# 2_Isolation.net
KiCad netlist of a schematic drawn in Altium Designer
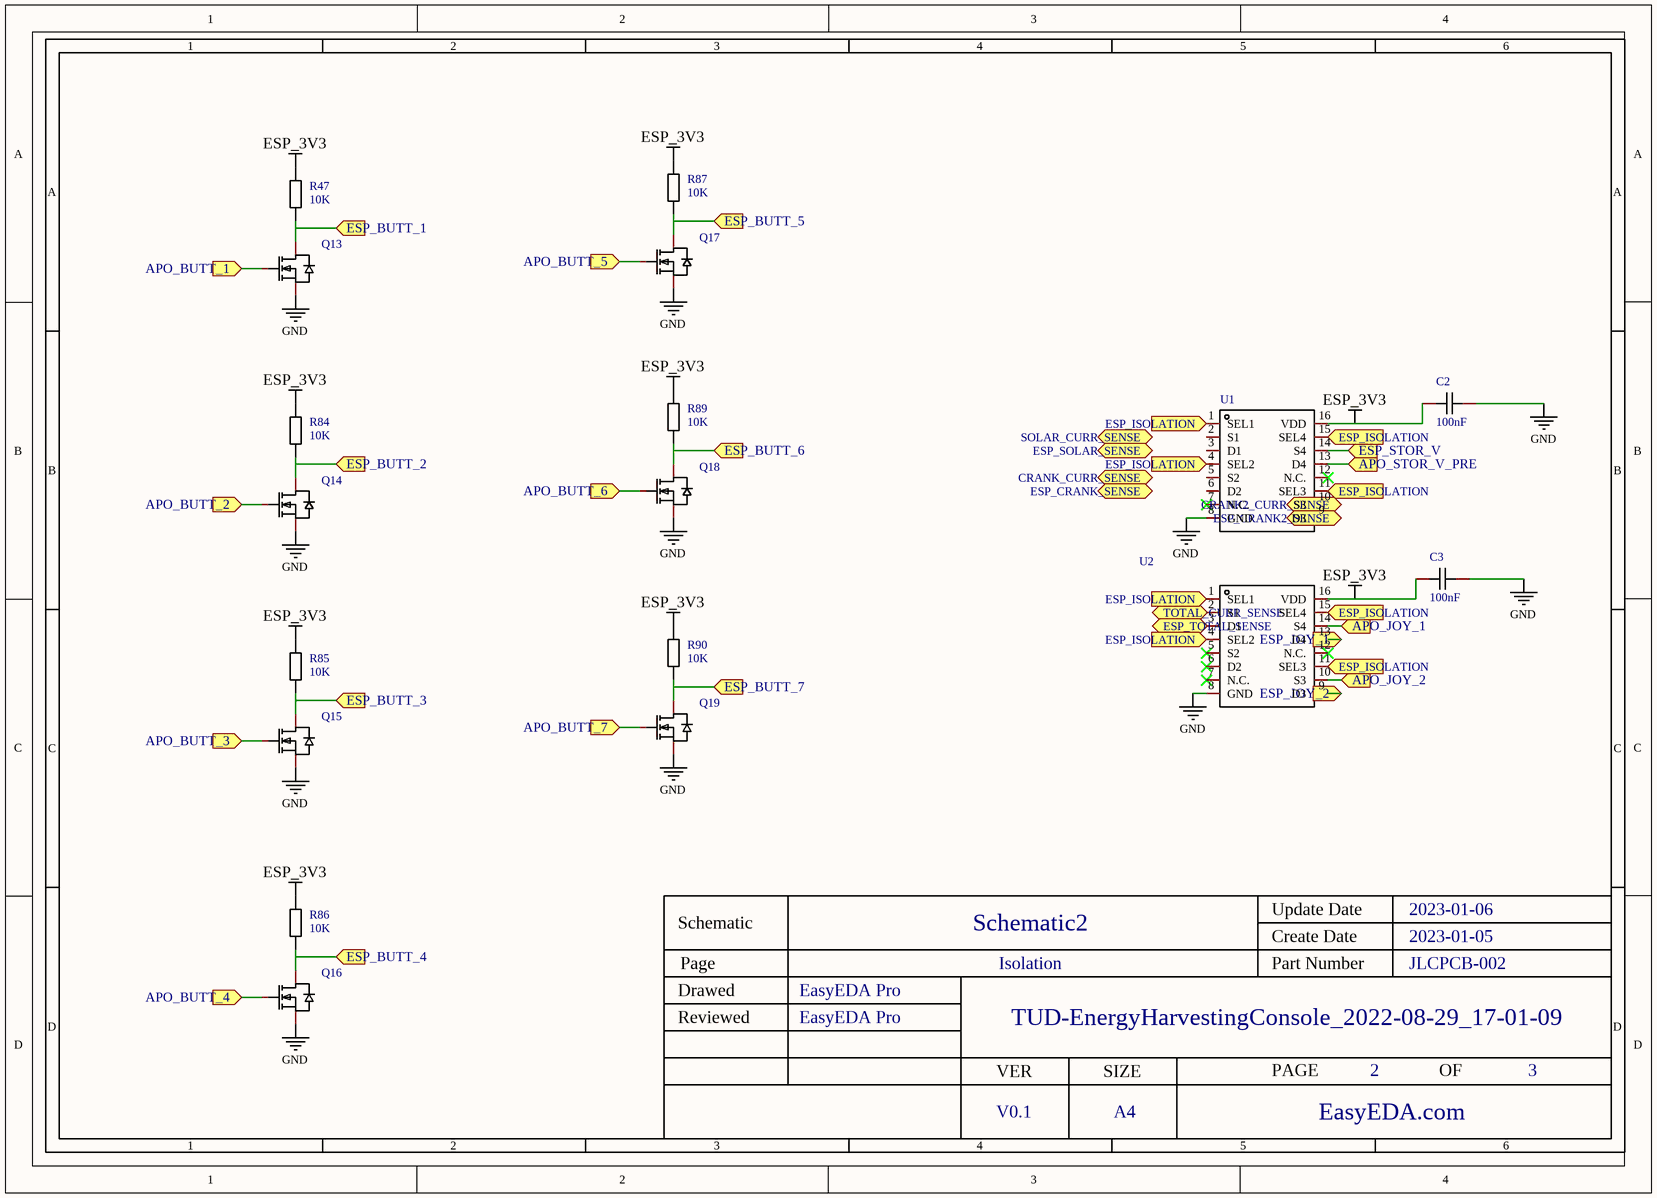
[diagram p0: 2_Isolation.schdoc]

(export (version "E")
  (design (tool "Eeschema 10.0.6"))
  (components
    (comp (ref "C2")
      (value "100nF")
      (fields
        (field (name "NAME") "100nF")
        (field (name "MANUFACTURER") "YAGEO")
        (field (name "MANUFACTURER PART") "CC0603KRX7R9BB104")
      )
      (libsource (lib "altium-import") (part "root_2_CC0603KRX7R9BB104_"))
    )
    (comp (ref "C3")
      (value "100nF")
      (fields
        (field (name "NAME") "100nF")
        (field (name "MANUFACTURER") "YAGEO")
        (field (name "MANUFACTURER PART") "CC0603KRX7R9BB104")
      )
      (libsource (lib "altium-import") (part "root_0_CC0603KRX7R9BB104_"))
    )
    (comp (ref "Q13")
      (value "SI2302")
      (fields (field (name "MANUFACTURER") "YONGYUTAI(永裕泰)"))
      (libsource (lib "altium-import") (part "root_0_SI2302_"))
    )
    (comp (ref "Q14")
      (value "SI2302")
      (fields (field (name "MANUFACTURER") "YONGYUTAI(永裕泰)"))
      (libsource (lib "altium-import") (part "root_0_SI2302_"))
    )
    (comp (ref "Q15")
      (value "SI2302")
      (fields (field (name "MANUFACTURER") "YONGYUTAI(永裕泰)"))
      (libsource (lib "altium-import") (part "root_0_SI2302_"))
    )
    (comp (ref "Q16")
      (value "SI2302")
      (fields (field (name "MANUFACTURER") "YONGYUTAI(永裕泰)"))
      (libsource (lib "altium-import") (part "root_0_SI2302_"))
    )
    (comp (ref "Q17")
      (value "SI2302")
      (fields (field (name "MANUFACTURER") "YONGYUTAI(永裕泰)"))
      (libsource (lib "altium-import") (part "root_0_SI2302_"))
    )
    (comp (ref "Q18")
      (value "SI2302")
      (fields (field (name "MANUFACTURER") "YONGYUTAI(永裕泰)"))
      (libsource (lib "altium-import") (part "root_0_SI2302_"))
    )
    (comp (ref "Q19")
      (value "SI2302")
      (fields (field (name "MANUFACTURER") "YONGYUTAI(永裕泰)"))
      (libsource (lib "altium-import") (part "root_0_SI2302_"))
    )
    (comp (ref "R47")
      (value "10K")
      (fields
        (field (name "NAME") "10K")
        (field (name "MANUFACTURER") "UniOhm")
        (field (name "MANUFACTURER PART") "0603WAF1002T5E")
      )
      (libsource (lib "altium-import") (part "root_3_0603WAF1002T5E_"))
    )
    (comp (ref "R84")
      (value "10K")
      (fields
        (field (name "NAME") "10K")
        (field (name "MANUFACTURER") "UniOhm")
        (field (name "MANUFACTURER PART") "0603WAF1002T5E")
      )
      (libsource (lib "altium-import") (part "root_3_0603WAF1002T5E_"))
    )
    (comp (ref "R85")
      (value "10K")
      (fields
        (field (name "NAME") "10K")
        (field (name "MANUFACTURER") "UniOhm")
        (field (name "MANUFACTURER PART") "0603WAF1002T5E")
      )
      (libsource (lib "altium-import") (part "root_3_0603WAF1002T5E_"))
    )
    (comp (ref "R86")
      (value "10K")
      (fields
        (field (name "NAME") "10K")
        (field (name "MANUFACTURER") "UniOhm")
        (field (name "MANUFACTURER PART") "0603WAF1002T5E")
      )
      (libsource (lib "altium-import") (part "root_3_0603WAF1002T5E_"))
    )
    (comp (ref "R87")
      (value "10K")
      (fields
        (field (name "NAME") "10K")
        (field (name "MANUFACTURER") "UniOhm")
        (field (name "MANUFACTURER PART") "0603WAF1002T5E")
      )
      (libsource (lib "altium-import") (part "root_3_0603WAF1002T5E_"))
    )
    (comp (ref "R89")
      (value "10K")
      (fields
        (field (name "NAME") "10K")
        (field (name "MANUFACTURER") "UniOhm")
        (field (name "MANUFACTURER PART") "0603WAF1002T5E")
      )
      (libsource (lib "altium-import") (part "root_3_0603WAF1002T5E_"))
    )
    (comp (ref "R90")
      (value "10K")
      (fields
        (field (name "NAME") "10K")
        (field (name "MANUFACTURER") "UniOhm")
        (field (name "MANUFACTURER PART") "0603WAF1002T5E")
      )
      (libsource (lib "altium-import") (part "root_3_0603WAF1002T5E_"))
    )
    (comp (ref "U1")
      (value "TMUX1511RSVR")
      (description "Switch Circuit:-")
      (fields (field (name "MANUFACTURER") "TI(德州仪器)"))
      (libsource (lib "altium-import") (part "root_0_TMUX1511RSVR_"))
    )
    (comp (ref "U2")
      (value "TMUX1511RSVR")
      (description "Switch Circuit:-")
      (fields (field (name "MANUFACTURER") "TI(德州仪器)"))
      (libsource (lib "altium-import") (part "root_0_TMUX1511RSVR_"))
    )
  )
  (nets
    (net (code "1") (name "/APO_BUTT_1") (class "Default")
      (node (ref "Q13") (pin "1") (pinfunction "G_1") (pintype "passive"))
    )
    (net (code "2") (name "/APO_BUTT_2") (class "Default")
      (node (ref "Q14") (pin "1") (pinfunction "G_1") (pintype "passive"))
    )
    (net (code "3") (name "/APO_BUTT_3") (class "Default")
      (node (ref "Q15") (pin "1") (pinfunction "G_1") (pintype "passive"))
    )
    (net (code "4") (name "/APO_BUTT_4") (class "Default")
      (node (ref "Q16") (pin "1") (pinfunction "G_1") (pintype "passive"))
    )
    (net (code "5") (name "/APO_BUTT_5") (class "Default")
      (node (ref "Q17") (pin "1") (pinfunction "G_1") (pintype "passive"))
    )
    (net (code "6") (name "/APO_BUTT_6") (class "Default")
      (node (ref "Q18") (pin "1") (pinfunction "G_1") (pintype "passive"))
    )
    (net (code "7") (name "/APO_BUTT_7") (class "Default")
      (node (ref "Q19") (pin "1") (pinfunction "G_1") (pintype "passive"))
    )
    (net (code "8") (name "/APO_JOY_1") (class "Default")
      (node (ref "U2") (pin "14") (pinfunction "S4_14") (pintype "passive"))
    )
    (net (code "9") (name "/APO_JOY_2") (class "Default")
      (node (ref "U2") (pin "10") (pinfunction "S3_10") (pintype "passive"))
    )
    (net (code "10") (name "/APO_STOR_V_PRE") (class "Default")
      (node (ref "U1") (pin "13") (pinfunction "D4_13") (pintype "passive"))
    )
    (net (code "13") (name "/ESP_BUTT_1") (class "Default")
      (node (ref "Q13") (pin "3") (pinfunction "D_3") (pintype "passive"))
      (node (ref "R47") (pin "2") (pinfunction "2_2") (pintype "passive"))
    )
    (net (code "14") (name "/ESP_BUTT_2") (class "Default")
      (node (ref "Q14") (pin "3") (pinfunction "D_3") (pintype "passive"))
      (node (ref "R84") (pin "2") (pinfunction "2_2") (pintype "passive"))
    )
    (net (code "15") (name "/ESP_BUTT_3") (class "Default")
      (node (ref "Q15") (pin "3") (pinfunction "D_3") (pintype "passive"))
      (node (ref "R85") (pin "2") (pinfunction "2_2") (pintype "passive"))
    )
    (net (code "16") (name "/ESP_BUTT_4") (class "Default")
      (node (ref "Q16") (pin "3") (pinfunction "D_3") (pintype "passive"))
      (node (ref "R86") (pin "2") (pinfunction "2_2") (pintype "passive"))
    )
    (net (code "17") (name "/ESP_BUTT_5") (class "Default")
      (node (ref "Q17") (pin "3") (pinfunction "D_3") (pintype "passive"))
      (node (ref "R87") (pin "2") (pinfunction "2_2") (pintype "passive"))
    )
    (net (code "18") (name "/ESP_BUTT_6") (class "Default")
      (node (ref "Q18") (pin "3") (pinfunction "D_3") (pintype "passive"))
      (node (ref "R89") (pin "2") (pinfunction "2_2") (pintype "passive"))
    )
    (net (code "19") (name "/ESP_BUTT_7") (class "Default")
      (node (ref "Q19") (pin "3") (pinfunction "D_3") (pintype "passive"))
      (node (ref "R90") (pin "2") (pinfunction "2_2") (pintype "passive"))
    )
    (net (code "22") (name "/ESP_ISOLATION") (class "Default")
      (node (ref "U1") (pin "1") (pinfunction "SEL1_1") (pintype "passive"))
      (node (ref "U1") (pin "11") (pinfunction "SEL3_11") (pintype "passive"))
      (node (ref "U1") (pin "15") (pinfunction "SEL4_15") (pintype "passive"))
      (node (ref "U1") (pin "4") (pinfunction "SEL2_4") (pintype "passive"))
      (node (ref "U2") (pin "1") (pinfunction "SEL1_1") (pintype "passive"))
      (node (ref "U2") (pin "11") (pinfunction "SEL3_11") (pintype "passive"))
      (node (ref "U2") (pin "15") (pinfunction "SEL4_15") (pintype "passive"))
      (node (ref "U2") (pin "4") (pinfunction "SEL2_4") (pintype "passive"))
    )
    (net (code "23") (name "/ESP_JOY_1") (class "Default")
      (node (ref "U2") (pin "13") (pinfunction "D4_13") (pintype "passive"))
    )
    (net (code "24") (name "/ESP_JOY_2") (class "Default")
      (node (ref "U2") (pin "9") (pinfunction "D3_9") (pintype "passive"))
    )
    (net (code "26") (name "/ESP_STOR_V") (class "Default")
      (node (ref "U1") (pin "14") (pinfunction "S4_14") (pintype "passive"))
    )
    (net (code "30") (name "ESP_3V3") (class "Default")
      (node (ref "C2") (pin "2") (pinfunction "2_2") (pintype "passive"))
      (node (ref "C3") (pin "1") (pinfunction "1_1") (pintype "passive"))
      (node (ref "R47") (pin "1") (pinfunction "1_1") (pintype "passive"))
      (node (ref "R84") (pin "1") (pinfunction "1_1") (pintype "passive"))
      (node (ref "R85") (pin "1") (pinfunction "1_1") (pintype "passive"))
      (node (ref "R86") (pin "1") (pinfunction "1_1") (pintype "passive"))
      (node (ref "R87") (pin "1") (pinfunction "1_1") (pintype "passive"))
      (node (ref "R89") (pin "1") (pinfunction "1_1") (pintype "passive"))
      (node (ref "R90") (pin "1") (pinfunction "1_1") (pintype "passive"))
      (node (ref "U1") (pin "16") (pinfunction "VDD_16") (pintype "passive"))
      (node (ref "U2") (pin "16") (pinfunction "VDD_16") (pintype "passive"))
    )
    (net (code "31") (name "GND") (class "Default")
      (node (ref "C2") (pin "1") (pinfunction "1_1") (pintype "passive"))
      (node (ref "C3") (pin "2") (pinfunction "2_2") (pintype "passive"))
      (node (ref "Q13") (pin "2") (pinfunction "S_2") (pintype "passive"))
      (node (ref "Q14") (pin "2") (pinfunction "S_2") (pintype "passive"))
      (node (ref "Q15") (pin "2") (pinfunction "S_2") (pintype "passive"))
      (node (ref "Q16") (pin "2") (pinfunction "S_2") (pintype "passive"))
      (node (ref "Q17") (pin "2") (pinfunction "S_2") (pintype "passive"))
      (node (ref "Q18") (pin "2") (pinfunction "S_2") (pintype "passive"))
      (node (ref "Q19") (pin "2") (pinfunction "S_2") (pintype "passive"))
      (node (ref "U1") (pin "8") (pinfunction "GND_8") (pintype "passive"))
      (node (ref "U2") (pin "8") (pinfunction "GND_8") (pintype "passive"))
    )
    (net (code "32") (name "unconnected-(U1-D1-Pad3)") (class "Default")
      (node (ref "U1") (pin "3") (pinfunction "D1_3") (pintype "passive"))
    )
    (net (code "33") (name "unconnected-(U1-D2-Pad6)") (class "Default")
      (node (ref "U1") (pin "6") (pinfunction "D2_6") (pintype "passive"))
    )
    (net (code "34") (name "unconnected-(U1-D3-Pad9)") (class "Default")
      (node (ref "U1") (pin "9") (pinfunction "D3_9") (pintype "passive"))
    )
    (net (code "35") (name "unconnected-(U1-N.C.-Pad7)") (class "Default")
      (node (ref "U1") (pin "7") (pinfunction "N.C._7") (pintype "passive+no_connect"))
    )
    (net (code "36") (name "unconnected-(U1-N.C.-Pad12)") (class "Default")
      (node (ref "U1") (pin "12") (pinfunction "N.C._12") (pintype "passive+no_connect"))
    )
    (net (code "37") (name "unconnected-(U1-S1-Pad2)") (class "Default")
      (node (ref "U1") (pin "2") (pinfunction "S1_2") (pintype "passive"))
    )
    (net (code "38") (name "unconnected-(U1-S2-Pad5)") (class "Default")
      (node (ref "U1") (pin "5") (pinfunction "S2_5") (pintype "passive"))
    )
    (net (code "39") (name "unconnected-(U1-S3-Pad10)") (class "Default")
      (node (ref "U1") (pin "10") (pinfunction "S3_10") (pintype "passive"))
    )
    (net (code "40") (name "unconnected-(U2-D1-Pad3)") (class "Default")
      (node (ref "U2") (pin "3") (pinfunction "D1_3") (pintype "passive"))
    )
    (net (code "41") (name "unconnected-(U2-D2-Pad6)") (class "Default")
      (node (ref "U2") (pin "6") (pinfunction "D2_6") (pintype "passive+no_connect"))
    )
    (net (code "42") (name "unconnected-(U2-N.C.-Pad7)") (class "Default")
      (node (ref "U2") (pin "7") (pinfunction "N.C._7") (pintype "passive+no_connect"))
    )
    (net (code "43") (name "unconnected-(U2-N.C.-Pad12)") (class "Default")
      (node (ref "U2") (pin "12") (pinfunction "N.C._12") (pintype "passive+no_connect"))
    )
    (net (code "44") (name "unconnected-(U2-S1-Pad2)") (class "Default")
      (node (ref "U2") (pin "2") (pinfunction "S1_2") (pintype "passive"))
    )
    (net (code "45") (name "unconnected-(U2-S2-Pad5)") (class "Default")
      (node (ref "U2") (pin "5") (pinfunction "S2_5") (pintype "passive+no_connect"))
    )
  )
)
